# tanima-th.net
KiCad netlist of a schematic drawn in EAGLE
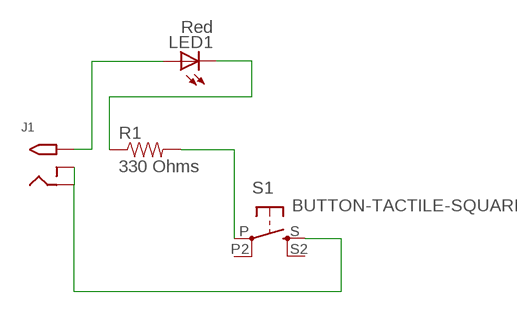
[diagram p0: schematic, sheet 1]

(export (version "E")
  (design (tool "Eeschema 10.0.6"))
  (components
    (comp (ref "J1")
      (value "2.1MMJACKTHM")
      (footprint "eagle-import:PJ-102A")
      (libsource (lib "eagle-import") (part "2.1MMJACKTHM"))
    )
    (comp (ref "LED1")
      (value "Red")
      (footprint "eagle-import:LED5MM")
      (libsource (lib "eagle-import") (part "LED5MM"))
    )
    (comp (ref "R1")
      (value "330 Ohms")
      (footprint "eagle-import:AXIAL-0.3")
      (libsource (lib "eagle-import") (part "RESISTORAXIAL-0.3"))
    )
    (comp (ref "S1")
      (value "BUTTON-TACTILE-SQUARE")
      (footprint "eagle-import:BUTTON-TACTILE-SQUARE-ADAFRUIT1010")
      (libsource (lib "eagle-import") (part "BUTTON-TACTILE-SQUARE"))
    )
  )
  (nets
    (net (code "1") (name "Net-(J1-PadRING)") (class "Default")
      (node (ref "J1") (pin "RING") (pinfunction "RING_RING") (pintype "bidirectional"))
      (node (ref "J1") (pin "RING_SW") (pinfunction "RING_SW_RING_SW") (pintype "bidirectional"))
      (node (ref "S1") (pin "S") (pinfunction "S_S") (pintype "passive"))
    )
    (net (code "2") (name "Net-(J1-PadTIP)") (class "Default")
      (node (ref "J1") (pin "TIP") (pinfunction "TIP_TIP") (pintype "bidirectional"))
      (node (ref "LED1") (pin "A") (pinfunction "A_A") (pintype "passive"))
    )
    (net (code "3") (name "Net-(LED1-C)") (class "Default")
      (node (ref "LED1") (pin "K") (pinfunction "C_K") (pintype "passive"))
      (node (ref "R1") (pin "P$1") (pinfunction "1_P$1") (pintype "passive"))
    )
    (net (code "4") (name "Net-(R1-2)") (class "Default")
      (node (ref "R1") (pin "P$2") (pinfunction "2_P$2") (pintype "passive"))
      (node (ref "S1") (pin "P") (pinfunction "P_P") (pintype "passive"))
    )
    (net (code "5") (name "unconnected-(S1-P1-PadP2)") (class "Default")
      (node (ref "S1") (pin "P2") (pinfunction "P1_P2") (pintype "passive"))
    )
    (net (code "6") (name "unconnected-(S1-S1-PadS2)") (class "Default")
      (node (ref "S1") (pin "S2") (pinfunction "S1_S2") (pintype "passive"))
    )
  )
)
